# 14_segment.net
KiCad netlist of a schematic drawn in Altium Designer
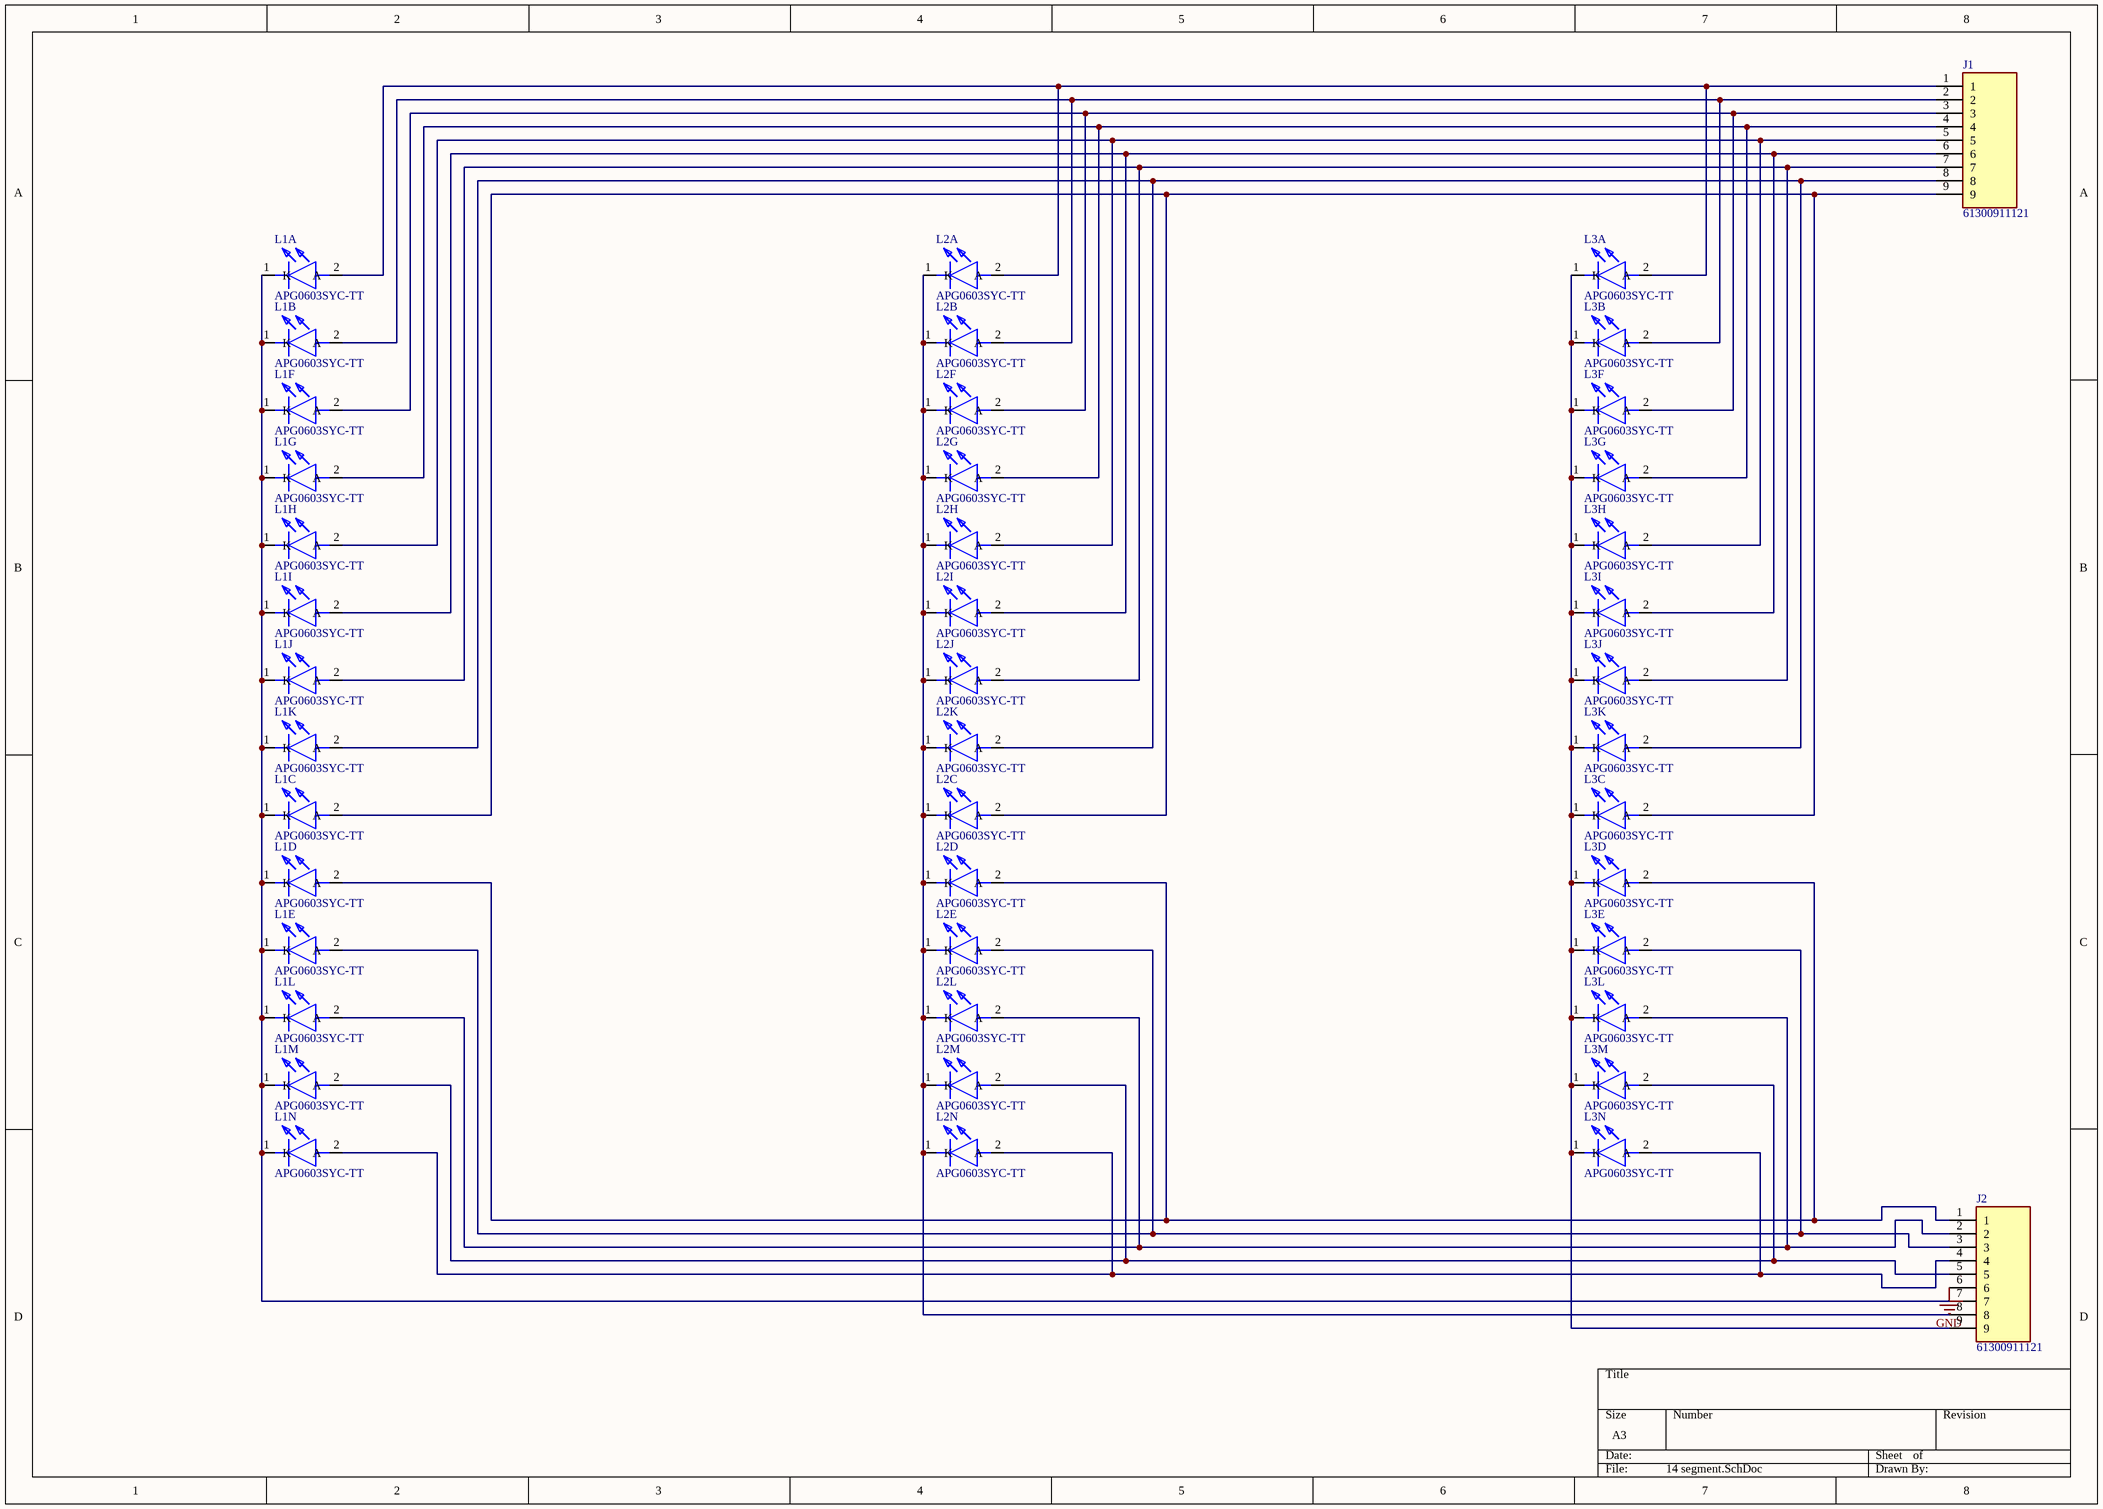
[diagram p0: 14 segment.SchDoc]

(export (version "E")
  (design (tool "Eeschema 10.0.6"))
  (components
    (comp (ref "J1")
      (value "61300911121")
      (footprint "SamacSys:HDRV9W95P0X254_1X9_2286X254X874P")
      (description "Connector")
      (fields (field (name "MOUSER PART NUMBER") "710-61300911121"))
      (libsource (lib "*") (part "61300911121"))
    )
    (comp (ref "J2")
      (value "61300911121")
      (footprint "SamacSys:HDRV9W95P0X254_1X9_2286X254X874P")
      (description "Connector")
      (fields (field (name "MOUSER PART NUMBER") "710-61300911121"))
      (libsource (lib "*") (part "61300911121"))
    )
    (comp (ref "L1A")
      (value "APG0603SYC-TT")
      (footprint "SamacSys:APG0603SYCTT")
      (description "LED")
      (fields (field (name "MOUSER PART NUMBER") "604-APG0603SYCTT"))
      (libsource (lib "*") (part "APG0603SYC-TT"))
    )
    (comp (ref "L1B")
      (value "APG0603SYC-TT")
      (footprint "SamacSys:APG0603SYCTT")
      (description "LED")
      (fields (field (name "MOUSER PART NUMBER") "604-APG0603SYCTT"))
      (libsource (lib "*") (part "APG0603SYC-TT"))
    )
    (comp (ref "L1C")
      (value "APG0603SYC-TT")
      (footprint "SamacSys:APG0603SYCTT")
      (description "LED")
      (fields (field (name "MOUSER PART NUMBER") "604-APG0603SYCTT"))
      (libsource (lib "*") (part "APG0603SYC-TT"))
    )
    (comp (ref "L1D")
      (value "APG0603SYC-TT")
      (footprint "SamacSys:APG0603SYCTT")
      (description "LED")
      (fields (field (name "MOUSER PART NUMBER") "604-APG0603SYCTT"))
      (libsource (lib "*") (part "APG0603SYC-TT"))
    )
    (comp (ref "L1E")
      (value "APG0603SYC-TT")
      (footprint "SamacSys:APG0603SYCTT")
      (description "LED")
      (fields (field (name "MOUSER PART NUMBER") "604-APG0603SYCTT"))
      (libsource (lib "*") (part "APG0603SYC-TT"))
    )
    (comp (ref "L1F")
      (value "APG0603SYC-TT")
      (footprint "SamacSys:APG0603SYCTT")
      (description "LED")
      (fields (field (name "MOUSER PART NUMBER") "604-APG0603SYCTT"))
      (libsource (lib "*") (part "APG0603SYC-TT"))
    )
    (comp (ref "L1G")
      (value "APG0603SYC-TT")
      (footprint "SamacSys:APG0603SYCTT")
      (description "LED")
      (fields (field (name "MOUSER PART NUMBER") "604-APG0603SYCTT"))
      (libsource (lib "*") (part "APG0603SYC-TT"))
    )
    (comp (ref "L1H")
      (value "APG0603SYC-TT")
      (footprint "SamacSys:APG0603SYCTT")
      (description "LED")
      (fields (field (name "MOUSER PART NUMBER") "604-APG0603SYCTT"))
      (libsource (lib "*") (part "APG0603SYC-TT"))
    )
    (comp (ref "L1I")
      (value "APG0603SYC-TT")
      (footprint "SamacSys:APG0603SYCTT")
      (description "LED")
      (fields (field (name "MOUSER PART NUMBER") "604-APG0603SYCTT"))
      (libsource (lib "*") (part "APG0603SYC-TT"))
    )
    (comp (ref "L1J")
      (value "APG0603SYC-TT")
      (footprint "SamacSys:APG0603SYCTT")
      (description "LED")
      (fields (field (name "MOUSER PART NUMBER") "604-APG0603SYCTT"))
      (libsource (lib "*") (part "APG0603SYC-TT"))
    )
    (comp (ref "L1K")
      (value "APG0603SYC-TT")
      (footprint "SamacSys:APG0603SYCTT")
      (description "LED")
      (fields (field (name "MOUSER PART NUMBER") "604-APG0603SYCTT"))
      (libsource (lib "*") (part "APG0603SYC-TT"))
    )
    (comp (ref "L1L")
      (value "APG0603SYC-TT")
      (footprint "SamacSys:APG0603SYCTT")
      (description "LED")
      (fields (field (name "MOUSER PART NUMBER") "604-APG0603SYCTT"))
      (libsource (lib "*") (part "APG0603SYC-TT"))
    )
    (comp (ref "L1M")
      (value "APG0603SYC-TT")
      (footprint "SamacSys:APG0603SYCTT")
      (description "LED")
      (fields (field (name "MOUSER PART NUMBER") "604-APG0603SYCTT"))
      (libsource (lib "*") (part "APG0603SYC-TT"))
    )
    (comp (ref "L1N")
      (value "APG0603SYC-TT")
      (footprint "SamacSys:APG0603SYCTT")
      (description "LED")
      (fields (field (name "MOUSER PART NUMBER") "604-APG0603SYCTT"))
      (libsource (lib "*") (part "APG0603SYC-TT"))
    )
    (comp (ref "L2A")
      (value "APG0603SYC-TT")
      (footprint "SamacSys:APG0603SYCTT")
      (description "LED")
      (fields (field (name "MOUSER PART NUMBER") "604-APG0603SYCTT"))
      (libsource (lib "*") (part "APG0603SYC-TT"))
    )
    (comp (ref "L2B")
      (value "APG0603SYC-TT")
      (footprint "SamacSys:APG0603SYCTT")
      (description "LED")
      (fields (field (name "MOUSER PART NUMBER") "604-APG0603SYCTT"))
      (libsource (lib "*") (part "APG0603SYC-TT"))
    )
    (comp (ref "L2C")
      (value "APG0603SYC-TT")
      (footprint "SamacSys:APG0603SYCTT")
      (description "LED")
      (fields (field (name "MOUSER PART NUMBER") "604-APG0603SYCTT"))
      (libsource (lib "*") (part "APG0603SYC-TT"))
    )
    (comp (ref "L2D")
      (value "APG0603SYC-TT")
      (footprint "SamacSys:APG0603SYCTT")
      (description "LED")
      (fields (field (name "MOUSER PART NUMBER") "604-APG0603SYCTT"))
      (libsource (lib "*") (part "APG0603SYC-TT"))
    )
    (comp (ref "L2E")
      (value "APG0603SYC-TT")
      (footprint "SamacSys:APG0603SYCTT")
      (description "LED")
      (fields (field (name "MOUSER PART NUMBER") "604-APG0603SYCTT"))
      (libsource (lib "*") (part "APG0603SYC-TT"))
    )
    (comp (ref "L2F")
      (value "APG0603SYC-TT")
      (footprint "SamacSys:APG0603SYCTT")
      (description "LED")
      (fields (field (name "MOUSER PART NUMBER") "604-APG0603SYCTT"))
      (libsource (lib "*") (part "APG0603SYC-TT"))
    )
    (comp (ref "L2G")
      (value "APG0603SYC-TT")
      (footprint "SamacSys:APG0603SYCTT")
      (description "LED")
      (fields (field (name "MOUSER PART NUMBER") "604-APG0603SYCTT"))
      (libsource (lib "*") (part "APG0603SYC-TT"))
    )
    (comp (ref "L2H")
      (value "APG0603SYC-TT")
      (footprint "SamacSys:APG0603SYCTT")
      (description "LED")
      (fields (field (name "MOUSER PART NUMBER") "604-APG0603SYCTT"))
      (libsource (lib "*") (part "APG0603SYC-TT"))
    )
    (comp (ref "L2I")
      (value "APG0603SYC-TT")
      (footprint "SamacSys:APG0603SYCTT")
      (description "LED")
      (fields (field (name "MOUSER PART NUMBER") "604-APG0603SYCTT"))
      (libsource (lib "*") (part "APG0603SYC-TT"))
    )
    (comp (ref "L2J")
      (value "APG0603SYC-TT")
      (footprint "SamacSys:APG0603SYCTT")
      (description "LED")
      (fields (field (name "MOUSER PART NUMBER") "604-APG0603SYCTT"))
      (libsource (lib "*") (part "APG0603SYC-TT"))
    )
    (comp (ref "L2K")
      (value "APG0603SYC-TT")
      (footprint "SamacSys:APG0603SYCTT")
      (description "LED")
      (fields (field (name "MOUSER PART NUMBER") "604-APG0603SYCTT"))
      (libsource (lib "*") (part "APG0603SYC-TT"))
    )
    (comp (ref "L2L")
      (value "APG0603SYC-TT")
      (footprint "SamacSys:APG0603SYCTT")
      (description "LED")
      (fields (field (name "MOUSER PART NUMBER") "604-APG0603SYCTT"))
      (libsource (lib "*") (part "APG0603SYC-TT"))
    )
    (comp (ref "L2M")
      (value "APG0603SYC-TT")
      (footprint "SamacSys:APG0603SYCTT")
      (description "LED")
      (fields (field (name "MOUSER PART NUMBER") "604-APG0603SYCTT"))
      (libsource (lib "*") (part "APG0603SYC-TT"))
    )
    (comp (ref "L2N")
      (value "APG0603SYC-TT")
      (footprint "SamacSys:APG0603SYCTT")
      (description "LED")
      (fields (field (name "MOUSER PART NUMBER") "604-APG0603SYCTT"))
      (libsource (lib "*") (part "APG0603SYC-TT"))
    )
    (comp (ref "L3A")
      (value "APG0603SYC-TT")
      (footprint "SamacSys:APG0603SYCTT")
      (description "LED")
      (fields (field (name "MOUSER PART NUMBER") "604-APG0603SYCTT"))
      (libsource (lib "*") (part "APG0603SYC-TT"))
    )
    (comp (ref "L3B")
      (value "APG0603SYC-TT")
      (footprint "SamacSys:APG0603SYCTT")
      (description "LED")
      (fields (field (name "MOUSER PART NUMBER") "604-APG0603SYCTT"))
      (libsource (lib "*") (part "APG0603SYC-TT"))
    )
    (comp (ref "L3C")
      (value "APG0603SYC-TT")
      (footprint "SamacSys:APG0603SYCTT")
      (description "LED")
      (fields (field (name "MOUSER PART NUMBER") "604-APG0603SYCTT"))
      (libsource (lib "*") (part "APG0603SYC-TT"))
    )
    (comp (ref "L3D")
      (value "APG0603SYC-TT")
      (footprint "SamacSys:APG0603SYCTT")
      (description "LED")
      (fields (field (name "MOUSER PART NUMBER") "604-APG0603SYCTT"))
      (libsource (lib "*") (part "APG0603SYC-TT"))
    )
    (comp (ref "L3E")
      (value "APG0603SYC-TT")
      (footprint "SamacSys:APG0603SYCTT")
      (description "LED")
      (fields (field (name "MOUSER PART NUMBER") "604-APG0603SYCTT"))
      (libsource (lib "*") (part "APG0603SYC-TT"))
    )
    (comp (ref "L3F")
      (value "APG0603SYC-TT")
      (footprint "SamacSys:APG0603SYCTT")
      (description "LED")
      (fields (field (name "MOUSER PART NUMBER") "604-APG0603SYCTT"))
      (libsource (lib "*") (part "APG0603SYC-TT"))
    )
    (comp (ref "L3G")
      (value "APG0603SYC-TT")
      (footprint "SamacSys:APG0603SYCTT")
      (description "LED")
      (fields (field (name "MOUSER PART NUMBER") "604-APG0603SYCTT"))
      (libsource (lib "*") (part "APG0603SYC-TT"))
    )
    (comp (ref "L3H")
      (value "APG0603SYC-TT")
      (footprint "SamacSys:APG0603SYCTT")
      (description "LED")
      (fields (field (name "MOUSER PART NUMBER") "604-APG0603SYCTT"))
      (libsource (lib "*") (part "APG0603SYC-TT"))
    )
    (comp (ref "L3I")
      (value "APG0603SYC-TT")
      (footprint "SamacSys:APG0603SYCTT")
      (description "LED")
      (fields (field (name "MOUSER PART NUMBER") "604-APG0603SYCTT"))
      (libsource (lib "*") (part "APG0603SYC-TT"))
    )
    (comp (ref "L3J")
      (value "APG0603SYC-TT")
      (footprint "SamacSys:APG0603SYCTT")
      (description "LED")
      (fields (field (name "MOUSER PART NUMBER") "604-APG0603SYCTT"))
      (libsource (lib "*") (part "APG0603SYC-TT"))
    )
    (comp (ref "L3K")
      (value "APG0603SYC-TT")
      (footprint "SamacSys:APG0603SYCTT")
      (description "LED")
      (fields (field (name "MOUSER PART NUMBER") "604-APG0603SYCTT"))
      (libsource (lib "*") (part "APG0603SYC-TT"))
    )
    (comp (ref "L3L")
      (value "APG0603SYC-TT")
      (footprint "SamacSys:APG0603SYCTT")
      (description "LED")
      (fields (field (name "MOUSER PART NUMBER") "604-APG0603SYCTT"))
      (libsource (lib "*") (part "APG0603SYC-TT"))
    )
    (comp (ref "L3M")
      (value "APG0603SYC-TT")
      (footprint "SamacSys:APG0603SYCTT")
      (description "LED")
      (fields (field (name "MOUSER PART NUMBER") "604-APG0603SYCTT"))
      (libsource (lib "*") (part "APG0603SYC-TT"))
    )
    (comp (ref "L3N")
      (value "APG0603SYC-TT")
      (footprint "SamacSys:APG0603SYCTT")
      (description "LED")
      (fields (field (name "MOUSER PART NUMBER") "604-APG0603SYCTT"))
      (libsource (lib "*") (part "APG0603SYC-TT"))
    )
  )
  (nets
    (net (code "1") (name "GND") (class "Default")
      (node (ref "J2") (pin "6") (pinfunction "6_6") (pintype "passive"))
    )
    (net (code "2") (name "Net-(L1A-A)") (class "Default")
      (node (ref "J1") (pin "1") (pinfunction "1_1") (pintype "passive"))
      (node (ref "L1A") (pin "2") (pinfunction "A_2") (pintype "passive"))
      (node (ref "L2A") (pin "2") (pinfunction "A_2") (pintype "passive"))
      (node (ref "L3A") (pin "2") (pinfunction "A_2") (pintype "passive"))
    )
    (net (code "3") (name "Net-(L1A-K)") (class "Default")
      (node (ref "J2") (pin "7") (pinfunction "7_7") (pintype "passive"))
      (node (ref "L1A") (pin "1") (pinfunction "K_1") (pintype "passive"))
      (node (ref "L1B") (pin "1") (pinfunction "K_1") (pintype "passive"))
      (node (ref "L1C") (pin "1") (pinfunction "K_1") (pintype "passive"))
      (node (ref "L1D") (pin "1") (pinfunction "K_1") (pintype "passive"))
      (node (ref "L1E") (pin "1") (pinfunction "K_1") (pintype "passive"))
      (node (ref "L1F") (pin "1") (pinfunction "K_1") (pintype "passive"))
      (node (ref "L1G") (pin "1") (pinfunction "K_1") (pintype "passive"))
      (node (ref "L1H") (pin "1") (pinfunction "K_1") (pintype "passive"))
      (node (ref "L1I") (pin "1") (pinfunction "K_1") (pintype "passive"))
      (node (ref "L1J") (pin "1") (pinfunction "K_1") (pintype "passive"))
      (node (ref "L1K") (pin "1") (pinfunction "K_1") (pintype "passive"))
      (node (ref "L1L") (pin "1") (pinfunction "K_1") (pintype "passive"))
      (node (ref "L1M") (pin "1") (pinfunction "K_1") (pintype "passive"))
      (node (ref "L1N") (pin "1") (pinfunction "K_1") (pintype "passive"))
    )
    (net (code "4") (name "Net-(L1B-A)") (class "Default")
      (node (ref "J1") (pin "2") (pinfunction "2_2") (pintype "passive"))
      (node (ref "L1B") (pin "2") (pinfunction "A_2") (pintype "passive"))
      (node (ref "L2B") (pin "2") (pinfunction "A_2") (pintype "passive"))
      (node (ref "L3B") (pin "2") (pinfunction "A_2") (pintype "passive"))
    )
    (net (code "5") (name "Net-(L1C-A)") (class "Default")
      (node (ref "J1") (pin "9") (pinfunction "9_9") (pintype "passive"))
      (node (ref "L1C") (pin "2") (pinfunction "A_2") (pintype "passive"))
      (node (ref "L2C") (pin "2") (pinfunction "A_2") (pintype "passive"))
      (node (ref "L3C") (pin "2") (pinfunction "A_2") (pintype "passive"))
    )
    (net (code "6") (name "Net-(L1D-A)") (class "Default")
      (node (ref "J2") (pin "1") (pinfunction "1_1") (pintype "passive"))
      (node (ref "L1D") (pin "2") (pinfunction "A_2") (pintype "passive"))
      (node (ref "L2D") (pin "2") (pinfunction "A_2") (pintype "passive"))
      (node (ref "L3D") (pin "2") (pinfunction "A_2") (pintype "passive"))
    )
    (net (code "7") (name "Net-(L1E-A)") (class "Default")
      (node (ref "J2") (pin "3") (pinfunction "3_3") (pintype "passive"))
      (node (ref "L1E") (pin "2") (pinfunction "A_2") (pintype "passive"))
      (node (ref "L2E") (pin "2") (pinfunction "A_2") (pintype "passive"))
      (node (ref "L3E") (pin "2") (pinfunction "A_2") (pintype "passive"))
    )
    (net (code "8") (name "Net-(L1F-A)") (class "Default")
      (node (ref "J1") (pin "3") (pinfunction "3_3") (pintype "passive"))
      (node (ref "L1F") (pin "2") (pinfunction "A_2") (pintype "passive"))
      (node (ref "L2F") (pin "2") (pinfunction "A_2") (pintype "passive"))
      (node (ref "L3F") (pin "2") (pinfunction "A_2") (pintype "passive"))
    )
    (net (code "9") (name "Net-(L1G-A)") (class "Default")
      (node (ref "J1") (pin "4") (pinfunction "4_4") (pintype "passive"))
      (node (ref "L1G") (pin "2") (pinfunction "A_2") (pintype "passive"))
      (node (ref "L2G") (pin "2") (pinfunction "A_2") (pintype "passive"))
      (node (ref "L3G") (pin "2") (pinfunction "A_2") (pintype "passive"))
    )
    (net (code "10") (name "Net-(L1H-A)") (class "Default")
      (node (ref "J1") (pin "5") (pinfunction "5_5") (pintype "passive"))
      (node (ref "L1H") (pin "2") (pinfunction "A_2") (pintype "passive"))
      (node (ref "L2H") (pin "2") (pinfunction "A_2") (pintype "passive"))
      (node (ref "L3H") (pin "2") (pinfunction "A_2") (pintype "passive"))
    )
    (net (code "11") (name "Net-(L1I-A)") (class "Default")
      (node (ref "J1") (pin "6") (pinfunction "6_6") (pintype "passive"))
      (node (ref "L1I") (pin "2") (pinfunction "A_2") (pintype "passive"))
      (node (ref "L2I") (pin "2") (pinfunction "A_2") (pintype "passive"))
      (node (ref "L3I") (pin "2") (pinfunction "A_2") (pintype "passive"))
    )
    (net (code "12") (name "Net-(L1J-A)") (class "Default")
      (node (ref "J1") (pin "7") (pinfunction "7_7") (pintype "passive"))
      (node (ref "L1J") (pin "2") (pinfunction "A_2") (pintype "passive"))
      (node (ref "L2J") (pin "2") (pinfunction "A_2") (pintype "passive"))
      (node (ref "L3J") (pin "2") (pinfunction "A_2") (pintype "passive"))
    )
    (net (code "13") (name "Net-(L1K-A)") (class "Default")
      (node (ref "J1") (pin "8") (pinfunction "8_8") (pintype "passive"))
      (node (ref "L1K") (pin "2") (pinfunction "A_2") (pintype "passive"))
      (node (ref "L2K") (pin "2") (pinfunction "A_2") (pintype "passive"))
      (node (ref "L3K") (pin "2") (pinfunction "A_2") (pintype "passive"))
    )
    (net (code "14") (name "Net-(L1L-A)") (class "Default")
      (node (ref "J2") (pin "2") (pinfunction "2_2") (pintype "passive"))
      (node (ref "L1L") (pin "2") (pinfunction "A_2") (pintype "passive"))
      (node (ref "L2L") (pin "2") (pinfunction "A_2") (pintype "passive"))
      (node (ref "L3L") (pin "2") (pinfunction "A_2") (pintype "passive"))
    )
    (net (code "15") (name "Net-(L1M-A)") (class "Default")
      (node (ref "J2") (pin "5") (pinfunction "5_5") (pintype "passive"))
      (node (ref "L1M") (pin "2") (pinfunction "A_2") (pintype "passive"))
      (node (ref "L2M") (pin "2") (pinfunction "A_2") (pintype "passive"))
      (node (ref "L3M") (pin "2") (pinfunction "A_2") (pintype "passive"))
    )
    (net (code "16") (name "Net-(L1N-A)") (class "Default")
      (node (ref "J2") (pin "4") (pinfunction "4_4") (pintype "passive"))
      (node (ref "L1N") (pin "2") (pinfunction "A_2") (pintype "passive"))
      (node (ref "L2N") (pin "2") (pinfunction "A_2") (pintype "passive"))
      (node (ref "L3N") (pin "2") (pinfunction "A_2") (pintype "passive"))
    )
    (net (code "17") (name "Net-(L2A-K)") (class "Default")
      (node (ref "J2") (pin "8") (pinfunction "8_8") (pintype "passive"))
      (node (ref "L2A") (pin "1") (pinfunction "K_1") (pintype "passive"))
      (node (ref "L2B") (pin "1") (pinfunction "K_1") (pintype "passive"))
      (node (ref "L2C") (pin "1") (pinfunction "K_1") (pintype "passive"))
      (node (ref "L2D") (pin "1") (pinfunction "K_1") (pintype "passive"))
      (node (ref "L2E") (pin "1") (pinfunction "K_1") (pintype "passive"))
      (node (ref "L2F") (pin "1") (pinfunction "K_1") (pintype "passive"))
      (node (ref "L2G") (pin "1") (pinfunction "K_1") (pintype "passive"))
      (node (ref "L2H") (pin "1") (pinfunction "K_1") (pintype "passive"))
      (node (ref "L2I") (pin "1") (pinfunction "K_1") (pintype "passive"))
      (node (ref "L2J") (pin "1") (pinfunction "K_1") (pintype "passive"))
      (node (ref "L2K") (pin "1") (pinfunction "K_1") (pintype "passive"))
      (node (ref "L2L") (pin "1") (pinfunction "K_1") (pintype "passive"))
      (node (ref "L2M") (pin "1") (pinfunction "K_1") (pintype "passive"))
      (node (ref "L2N") (pin "1") (pinfunction "K_1") (pintype "passive"))
    )
    (net (code "18") (name "Net-(L3A-K)") (class "Default")
      (node (ref "J2") (pin "9") (pinfunction "9_9") (pintype "passive"))
      (node (ref "L3A") (pin "1") (pinfunction "K_1") (pintype "passive"))
      (node (ref "L3B") (pin "1") (pinfunction "K_1") (pintype "passive"))
      (node (ref "L3C") (pin "1") (pinfunction "K_1") (pintype "passive"))
      (node (ref "L3D") (pin "1") (pinfunction "K_1") (pintype "passive"))
      (node (ref "L3E") (pin "1") (pinfunction "K_1") (pintype "passive"))
      (node (ref "L3F") (pin "1") (pinfunction "K_1") (pintype "passive"))
      (node (ref "L3G") (pin "1") (pinfunction "K_1") (pintype "passive"))
      (node (ref "L3H") (pin "1") (pinfunction "K_1") (pintype "passive"))
      (node (ref "L3I") (pin "1") (pinfunction "K_1") (pintype "passive"))
      (node (ref "L3J") (pin "1") (pinfunction "K_1") (pintype "passive"))
      (node (ref "L3K") (pin "1") (pinfunction "K_1") (pintype "passive"))
      (node (ref "L3L") (pin "1") (pinfunction "K_1") (pintype "passive"))
      (node (ref "L3M") (pin "1") (pinfunction "K_1") (pintype "passive"))
      (node (ref "L3N") (pin "1") (pinfunction "K_1") (pintype "passive"))
    )
  )
)
